# Ex_Controller.net
KiCad netlist of a schematic drawn in EAGLE
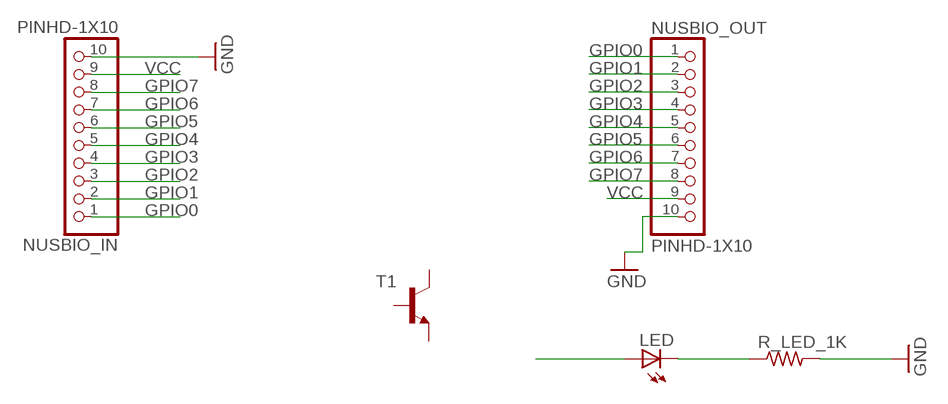
[diagram p0: schematic, sheet 1]

(export (version "E")
  (design (tool "Eeschema 10.0.6"))
  (components
    (comp (ref "LED")
      (value "LEDCHIPLED_0805")
      (footprint "eagle-import:CHIPLED_0805")
      (libsource (lib "eagle-import") (part "LEDCHIPLED_0805"))
    )
    (comp (ref "NUSBIO_IN")
      (value "PINHD-1X10")
      (footprint "eagle-import:1X10-BIG")
      (libsource (lib "eagle-import") (part "PINHD-1X10"))
    )
    (comp (ref "NUSBIO_OUT")
      (value "PINHD-1X10")
      (footprint "eagle-import:1X10-BIG")
      (libsource (lib "eagle-import") (part "PINHD-1X10"))
    )
    (comp (ref "R_LED_1K")
      (value "R-US_R0805")
      (footprint "eagle-import:R0805")
      (libsource (lib "eagle-import") (part "R-US_R0805"))
    )
    (comp (ref "T1")
      (value "MMBT3904LT1-NPN-SOT23-BEC")
      (footprint "eagle-import:SOT23-BEC")
      (libsource (lib "eagle-import") (part "-NPN-SOT23-BECMMBT3904LT1"))
    )
  )
  (nets
    (net (code "1") (name "/GPIO0") (class "Default")
      (node (ref "NUSBIO_IN") (pin "1") (pinfunction "1_1") (pintype "passive"))
      (node (ref "NUSBIO_OUT") (pin "1") (pinfunction "1_1") (pintype "passive"))
    )
    (net (code "2") (name "/GPIO1") (class "Default")
      (node (ref "NUSBIO_IN") (pin "2") (pinfunction "2_2") (pintype "passive"))
      (node (ref "NUSBIO_OUT") (pin "2") (pinfunction "2_2") (pintype "passive"))
    )
    (net (code "3") (name "/GPIO2") (class "Default")
      (node (ref "NUSBIO_IN") (pin "3") (pinfunction "3_3") (pintype "passive"))
      (node (ref "NUSBIO_OUT") (pin "3") (pinfunction "3_3") (pintype "passive"))
    )
    (net (code "4") (name "/GPIO3") (class "Default")
      (node (ref "NUSBIO_IN") (pin "4") (pinfunction "4_4") (pintype "passive"))
      (node (ref "NUSBIO_OUT") (pin "4") (pinfunction "4_4") (pintype "passive"))
    )
    (net (code "5") (name "/GPIO4") (class "Default")
      (node (ref "NUSBIO_IN") (pin "5") (pinfunction "5_5") (pintype "passive"))
      (node (ref "NUSBIO_OUT") (pin "5") (pinfunction "5_5") (pintype "passive"))
    )
    (net (code "6") (name "/GPIO5") (class "Default")
      (node (ref "NUSBIO_IN") (pin "6") (pinfunction "6_6") (pintype "passive"))
      (node (ref "NUSBIO_OUT") (pin "6") (pinfunction "6_6") (pintype "passive"))
    )
    (net (code "7") (name "/GPIO6") (class "Default")
      (node (ref "NUSBIO_IN") (pin "7") (pinfunction "7_7") (pintype "passive"))
      (node (ref "NUSBIO_OUT") (pin "7") (pinfunction "7_7") (pintype "passive"))
    )
    (net (code "8") (name "/GPIO7") (class "Default")
      (node (ref "NUSBIO_IN") (pin "8") (pinfunction "8_8") (pintype "passive"))
      (node (ref "NUSBIO_OUT") (pin "8") (pinfunction "8_8") (pintype "passive"))
    )
    (net (code "9") (name "/VCC") (class "Default")
      (node (ref "NUSBIO_IN") (pin "9") (pinfunction "9_9") (pintype "passive"))
      (node (ref "NUSBIO_OUT") (pin "9") (pinfunction "9_9") (pintype "passive"))
    )
    (net (code "10") (name "GND") (class "Default")
      (node (ref "NUSBIO_IN") (pin "10") (pinfunction "10_10") (pintype "passive"))
      (node (ref "NUSBIO_OUT") (pin "10") (pinfunction "10_10") (pintype "passive"))
      (node (ref "R_LED_1K") (pin "2") (pinfunction "2_2") (pintype "passive"))
    )
    (net (code "11") (name "Net-(LED-PadC)") (class "Default")
      (node (ref "LED") (pin "C") (pinfunction "C_C") (pintype "passive"))
      (node (ref "R_LED_1K") (pin "1") (pinfunction "1_1") (pintype "passive"))
    )
    (net (code "12") (name "unconnected-(LED-PadA)") (class "Default")
      (node (ref "LED") (pin "A") (pinfunction "A_A") (pintype "passive"))
    )
    (net (code "13") (name "unconnected-(T1-PadB)") (class "Default")
      (node (ref "T1") (pin "B") (pinfunction "B_B") (pintype "passive"))
    )
    (net (code "14") (name "unconnected-(T1-PadC)") (class "Default")
      (node (ref "T1") (pin "C") (pinfunction "C_C") (pintype "passive"))
    )
    (net (code "15") (name "unconnected-(T1-PadE)") (class "Default")
      (node (ref "T1") (pin "E") (pinfunction "E_E") (pintype "passive"))
    )
  )
)
